# IO.net
KiCad netlist of a schematic drawn in Altium Designer
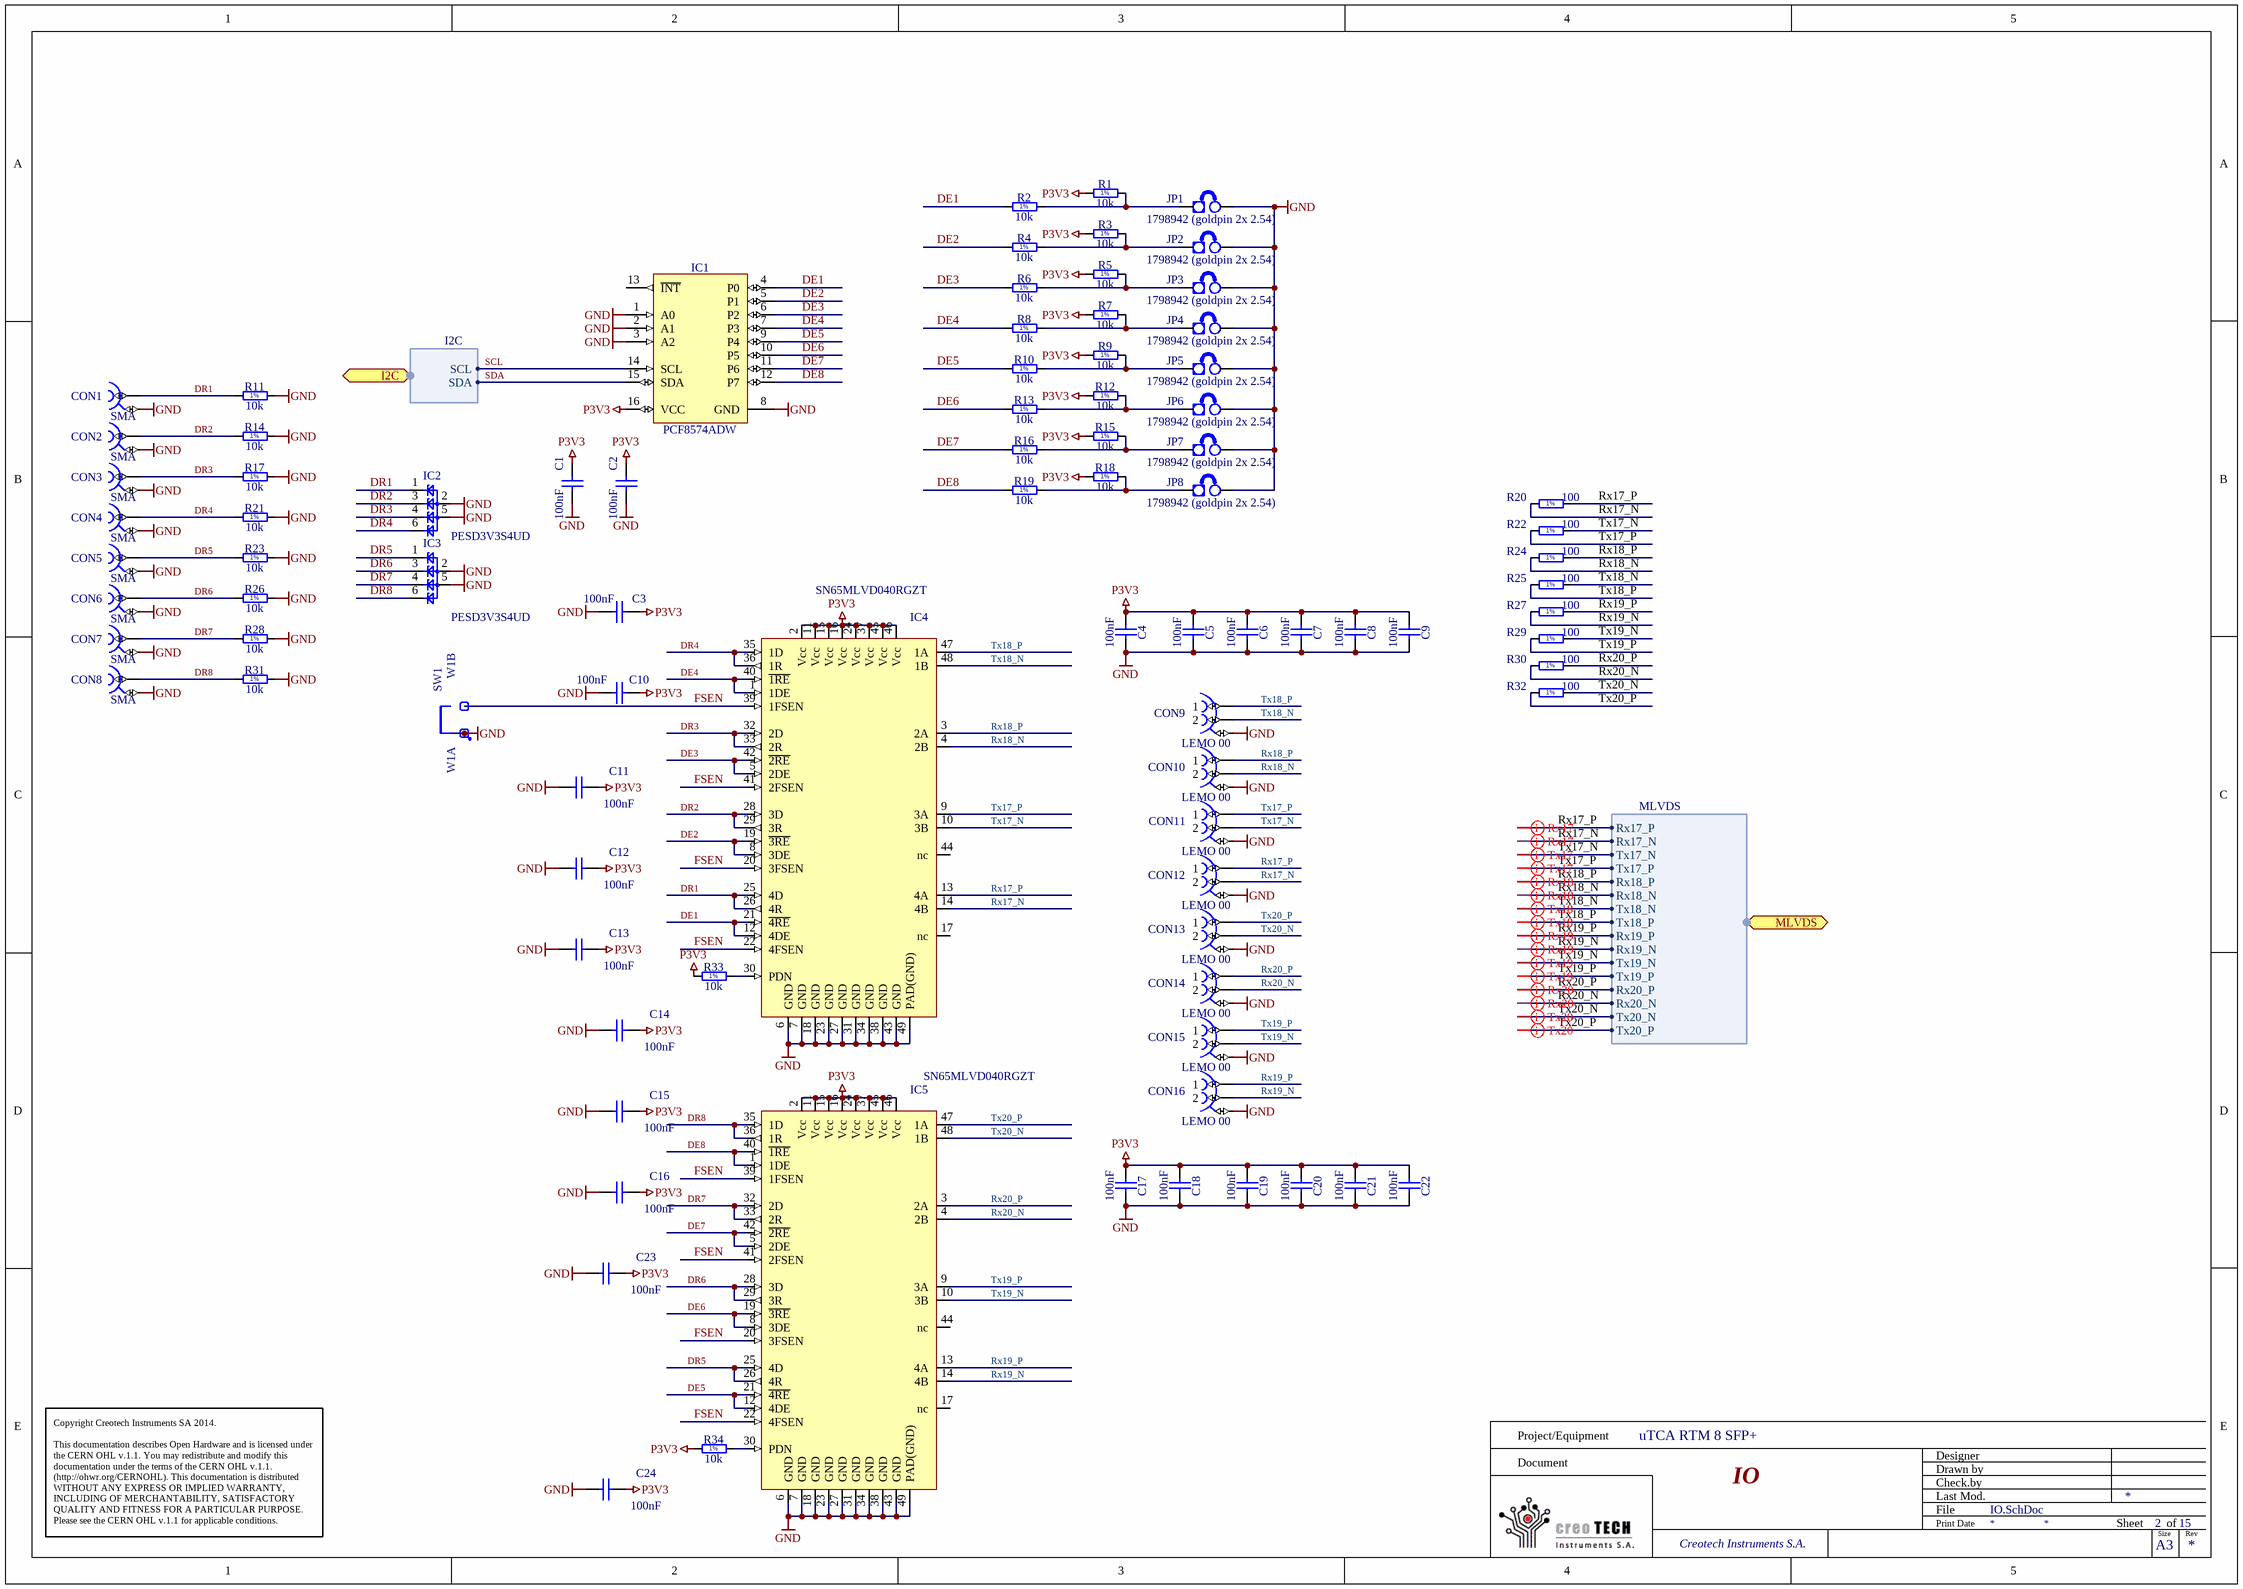
[diagram p0: IO.SchDoc]

(export (version "E")
  (design (tool "Eeschema 10.0.6"))
  (components
    (comp (ref "C1")
      (value "100nF")
      (footprint "CAPC0603X33N")
      (description "Non-polarised capacitor")
      (fields (field (name "PART NUMBER") "CC0201_100NF_6.3V_10%_X5R") (field (name "VOLTAGE") "6.3V"))
      (libsource (lib "Capacitors") (part "Capacitor - non polarized"))
    )
    (comp (ref "C2")
      (value "100nF")
      (footprint "CAPC0603X33N")
      (description "Non-polarised capacitor")
      (fields (field (name "PART NUMBER") "CC0201_100NF_6.3V_10%_X5R") (field (name "VOLTAGE") "6.3V"))
      (libsource (lib "Capacitors") (part "Capacitor - non polarized"))
    )
    (comp (ref "C3")
      (value "100nF")
      (footprint "CAPC0603X33N")
      (description "Non-polarised capacitor")
      (fields (field (name "PART NUMBER") "CC0201_100NF_6.3V_10%_X5R") (field (name "VOLTAGE") "6.3V"))
      (libsource (lib "Capacitors") (part "Capacitor - non polarized"))
    )
    (comp (ref "C4")
      (value "100nF")
      (footprint "CAPC0603X33N")
      (description "Non-polarised capacitor")
      (fields (field (name "PART NUMBER") "CC0201_100NF_6.3V_10%_X5R") (field (name "VOLTAGE") "6.3V"))
      (libsource (lib "Capacitors") (part "Capacitor - non polarized"))
    )
    (comp (ref "C5")
      (value "100nF")
      (footprint "CAPC0603X33N")
      (description "Non-polarised capacitor")
      (fields (field (name "PART NUMBER") "CC0201_100NF_6.3V_10%_X5R") (field (name "VOLTAGE") "6.3V"))
      (libsource (lib "Capacitors") (part "Capacitor - non polarized"))
    )
    (comp (ref "C6")
      (value "100nF")
      (footprint "CAPC0603X33N")
      (description "Non-polarised capacitor")
      (fields (field (name "PART NUMBER") "CC0201_100NF_6.3V_10%_X5R") (field (name "VOLTAGE") "6.3V"))
      (libsource (lib "Capacitors") (part "Capacitor - non polarized"))
    )
    (comp (ref "C7")
      (value "100nF")
      (footprint "CAPC0603X33N")
      (description "Non-polarised capacitor")
      (fields (field (name "PART NUMBER") "CC0201_100NF_6.3V_10%_X5R") (field (name "VOLTAGE") "6.3V"))
      (libsource (lib "Capacitors") (part "Capacitor - non polarized"))
    )
    (comp (ref "C8")
      (value "100nF")
      (footprint "CAPC0603X33N")
      (description "Non-polarised capacitor")
      (fields (field (name "PART NUMBER") "CC0201_100NF_6.3V_10%_X5R") (field (name "VOLTAGE") "6.3V"))
      (libsource (lib "Capacitors") (part "Capacitor - non polarized"))
    )
    (comp (ref "C9")
      (value "100nF")
      (footprint "CAPC0603X33N")
      (description "Non-polarised capacitor")
      (fields (field (name "PART NUMBER") "CC0201_100NF_6.3V_10%_X5R") (field (name "VOLTAGE") "6.3V"))
      (libsource (lib "Capacitors") (part "Capacitor - non polarized"))
    )
    (comp (ref "C10")
      (value "100nF")
      (footprint "CAPC0603X33N")
      (description "Non-polarised capacitor")
      (fields (field (name "PART NUMBER") "CC0201_100NF_6.3V_10%_X5R") (field (name "VOLTAGE") "6.3V"))
      (libsource (lib "Capacitors") (part "Capacitor - non polarized"))
    )
    (comp (ref "C11")
      (value "100nF")
      (footprint "CAPC0603X33N")
      (description "Non-polarised capacitor")
      (fields (field (name "PART NUMBER") "CC0201_100NF_6.3V_10%_X5R") (field (name "VOLTAGE") "6.3V"))
      (libsource (lib "Capacitors") (part "Capacitor - non polarized"))
    )
    (comp (ref "C12")
      (value "100nF")
      (footprint "CAPC0603X33N")
      (description "Non-polarised capacitor")
      (fields (field (name "PART NUMBER") "CC0201_100NF_6.3V_10%_X5R") (field (name "VOLTAGE") "6.3V"))
      (libsource (lib "Capacitors") (part "Capacitor - non polarized"))
    )
    (comp (ref "C13")
      (value "100nF")
      (footprint "CAPC0603X33N")
      (description "Non-polarised capacitor")
      (fields (field (name "PART NUMBER") "CC0201_100NF_6.3V_10%_X5R") (field (name "VOLTAGE") "6.3V"))
      (libsource (lib "Capacitors") (part "Capacitor - non polarized"))
    )
    (comp (ref "C14")
      (value "100nF")
      (footprint "CAPC0603X33N")
      (description "Non-polarised capacitor")
      (fields (field (name "PART NUMBER") "CC0201_100NF_6.3V_10%_X5R") (field (name "VOLTAGE") "6.3V"))
      (libsource (lib "Capacitors") (part "Capacitor - non polarized"))
    )
    (comp (ref "C15")
      (value "100nF")
      (footprint "CAPC0603X33N")
      (description "Non-polarised capacitor")
      (fields (field (name "PART NUMBER") "CC0201_100NF_6.3V_10%_X5R") (field (name "VOLTAGE") "6.3V"))
      (libsource (lib "Capacitors") (part "Capacitor - non polarized"))
    )
    (comp (ref "C16")
      (value "100nF")
      (footprint "CAPC0603X33N")
      (description "Non-polarised capacitor")
      (fields (field (name "PART NUMBER") "CC0201_100NF_6.3V_10%_X5R") (field (name "VOLTAGE") "6.3V"))
      (libsource (lib "Capacitors") (part "Capacitor - non polarized"))
    )
    (comp (ref "C17")
      (value "100nF")
      (footprint "CAPC0603X33N")
      (description "Non-polarised capacitor")
      (fields (field (name "PART NUMBER") "CC0201_100NF_6.3V_10%_X5R") (field (name "VOLTAGE") "6.3V"))
      (libsource (lib "Capacitors") (part "Capacitor - non polarized"))
    )
    (comp (ref "C18")
      (value "100nF")
      (footprint "CAPC0603X33N")
      (description "Non-polarised capacitor")
      (fields (field (name "PART NUMBER") "CC0201_100NF_6.3V_10%_X5R") (field (name "VOLTAGE") "6.3V"))
      (libsource (lib "Capacitors") (part "Capacitor - non polarized"))
    )
    (comp (ref "C19")
      (value "100nF")
      (footprint "CAPC0603X33N")
      (description "Non-polarised capacitor")
      (fields (field (name "PART NUMBER") "CC0201_100NF_6.3V_10%_X5R") (field (name "VOLTAGE") "6.3V"))
      (libsource (lib "Capacitors") (part "Capacitor - non polarized"))
    )
    (comp (ref "C20")
      (value "100nF")
      (footprint "CAPC0603X33N")
      (description "Non-polarised capacitor")
      (fields (field (name "PART NUMBER") "CC0201_100NF_6.3V_10%_X5R") (field (name "VOLTAGE") "6.3V"))
      (libsource (lib "Capacitors") (part "Capacitor - non polarized"))
    )
    (comp (ref "C21")
      (value "100nF")
      (footprint "CAPC0603X33N")
      (description "Non-polarised capacitor")
      (fields (field (name "PART NUMBER") "CC0201_100NF_6.3V_10%_X5R") (field (name "VOLTAGE") "6.3V"))
      (libsource (lib "Capacitors") (part "Capacitor - non polarized"))
    )
    (comp (ref "C22")
      (value "100nF")
      (footprint "CAPC0603X33N")
      (description "Non-polarised capacitor")
      (fields (field (name "PART NUMBER") "CC0201_100NF_6.3V_10%_X5R") (field (name "VOLTAGE") "6.3V"))
      (libsource (lib "Capacitors") (part "Capacitor - non polarized"))
    )
    (comp (ref "C23")
      (value "100nF")
      (footprint "CAPC0603X33N")
      (description "Non-polarised capacitor")
      (fields (field (name "PART NUMBER") "CC0201_100NF_6.3V_10%_X5R") (field (name "VOLTAGE") "6.3V"))
      (libsource (lib "Capacitors") (part "Capacitor - non polarized"))
    )
    (comp (ref "C24")
      (value "100nF")
      (footprint "CAPC0603X33N")
      (description "Non-polarised capacitor")
      (fields (field (name "PART NUMBER") "CC0201_100NF_6.3V_10%_X5R") (field (name "VOLTAGE") "6.3V"))
      (libsource (lib "Capacitors") (part "Capacitor - non polarized"))
    )
    (comp (ref "CON1")
      (value "SMA")
      (footprint "HUBER-SUHNER_85 SMA-50-0-101/111 NE")
      (fields
        (field (name "PART NUMBER") "HUBER-SUHNER_85_SMA-50-0-101/111_NE")
        (field (name "MANUFACTURER") "HUBER+SUHNER")
        (field (name "MANUFACTURER PART NUMBER") "85_SMA-50-0-101/111_NE")
      )
      (libsource (lib "Connectors") (part "Coax_1Female_1Shield"))
    )
    (comp (ref "CON2")
      (value "SMA")
      (footprint "HUBER-SUHNER_85 SMA-50-0-101/111 NE")
      (fields
        (field (name "PART NUMBER") "HUBER-SUHNER_85_SMA-50-0-101/111_NE")
        (field (name "MANUFACTURER") "HUBER+SUHNER")
        (field (name "MANUFACTURER PART NUMBER") "85_SMA-50-0-101/111_NE")
      )
      (libsource (lib "Connectors") (part "Coax_1Female_1Shield"))
    )
    (comp (ref "CON3")
      (value "SMA")
      (footprint "HUBER-SUHNER_85 SMA-50-0-101/111 NE")
      (fields
        (field (name "PART NUMBER") "HUBER-SUHNER_85_SMA-50-0-101/111_NE")
        (field (name "MANUFACTURER") "HUBER+SUHNER")
        (field (name "MANUFACTURER PART NUMBER") "85_SMA-50-0-101/111_NE")
      )
      (libsource (lib "Connectors") (part "Coax_1Female_1Shield"))
    )
    (comp (ref "CON4")
      (value "SMA")
      (footprint "HUBER-SUHNER_85 SMA-50-0-101/111 NE")
      (fields
        (field (name "PART NUMBER") "HUBER-SUHNER_85_SMA-50-0-101/111_NE")
        (field (name "MANUFACTURER") "HUBER+SUHNER")
        (field (name "MANUFACTURER PART NUMBER") "85_SMA-50-0-101/111_NE")
      )
      (libsource (lib "Connectors") (part "Coax_1Female_1Shield"))
    )
    (comp (ref "CON5")
      (value "SMA")
      (footprint "HUBER-SUHNER_85 SMA-50-0-101/111 NE")
      (fields
        (field (name "PART NUMBER") "HUBER-SUHNER_85_SMA-50-0-101/111_NE")
        (field (name "MANUFACTURER") "HUBER+SUHNER")
        (field (name "MANUFACTURER PART NUMBER") "85_SMA-50-0-101/111_NE")
      )
      (libsource (lib "Connectors") (part "Coax_1Female_1Shield"))
    )
    (comp (ref "CON6")
      (value "SMA")
      (footprint "HUBER-SUHNER_85 SMA-50-0-101/111 NE")
      (fields
        (field (name "PART NUMBER") "HUBER-SUHNER_85_SMA-50-0-101/111_NE")
        (field (name "MANUFACTURER") "HUBER+SUHNER")
        (field (name "MANUFACTURER PART NUMBER") "85_SMA-50-0-101/111_NE")
      )
      (libsource (lib "Connectors") (part "Coax_1Female_1Shield"))
    )
    (comp (ref "CON7")
      (value "SMA")
      (footprint "HUBER-SUHNER_85 SMA-50-0-101/111 NE")
      (fields
        (field (name "PART NUMBER") "HUBER-SUHNER_85_SMA-50-0-101/111_NE")
        (field (name "MANUFACTURER") "HUBER+SUHNER")
        (field (name "MANUFACTURER PART NUMBER") "85_SMA-50-0-101/111_NE")
      )
      (libsource (lib "Connectors") (part "Coax_1Female_1Shield"))
    )
    (comp (ref "CON8")
      (value "SMA")
      (footprint "HUBER-SUHNER_85 SMA-50-0-101/111 NE")
      (fields
        (field (name "PART NUMBER") "HUBER-SUHNER_85_SMA-50-0-101/111_NE")
        (field (name "MANUFACTURER") "HUBER+SUHNER")
        (field (name "MANUFACTURER PART NUMBER") "85_SMA-50-0-101/111_NE")
      )
      (libsource (lib "Connectors") (part "Coax_1Female_1Shield"))
    )
    (comp (ref "CON9")
      (value "LEMO 00")
      (footprint "LEMO_EPG.00.302.NLN")
      (fields
        (field (name "PART NUMBER") "LEMO_EPG.00.302.NLN")
        (field (name "MANUFACTURER") "LEMO")
        (field (name "MANUFACTURER PART NUMBER") "EPG.00.302.NLN")
      )
      (libsource (lib "Connectors") (part "Coax_2Female_1Shield"))
    )
    (comp (ref "CON10")
      (value "LEMO 00")
      (footprint "LEMO_EPG.00.302.NLN")
      (fields
        (field (name "PART NUMBER") "LEMO_EPG.00.302.NLN")
        (field (name "MANUFACTURER") "LEMO")
        (field (name "MANUFACTURER PART NUMBER") "EPG.00.302.NLN")
      )
      (libsource (lib "Connectors") (part "Coax_2Female_1Shield"))
    )
    (comp (ref "CON11")
      (value "LEMO 00")
      (footprint "LEMO_EPG.00.302.NLN")
      (fields
        (field (name "PART NUMBER") "LEMO_EPG.00.302.NLN")
        (field (name "MANUFACTURER") "LEMO")
        (field (name "MANUFACTURER PART NUMBER") "EPG.00.302.NLN")
      )
      (libsource (lib "Connectors") (part "Coax_2Female_1Shield"))
    )
    (comp (ref "CON12")
      (value "LEMO 00")
      (footprint "LEMO_EPG.00.302.NLN")
      (fields
        (field (name "PART NUMBER") "LEMO_EPG.00.302.NLN")
        (field (name "MANUFACTURER") "LEMO")
        (field (name "MANUFACTURER PART NUMBER") "EPG.00.302.NLN")
      )
      (libsource (lib "Connectors") (part "Coax_2Female_1Shield"))
    )
    (comp (ref "CON13")
      (value "LEMO 00")
      (footprint "LEMO_EPG.00.302.NLN")
      (fields
        (field (name "PART NUMBER") "LEMO_EPG.00.302.NLN")
        (field (name "MANUFACTURER") "LEMO")
        (field (name "MANUFACTURER PART NUMBER") "EPG.00.302.NLN")
      )
      (libsource (lib "Connectors") (part "Coax_2Female_1Shield"))
    )
    (comp (ref "CON14")
      (value "LEMO 00")
      (footprint "LEMO_EPG.00.302.NLN")
      (fields
        (field (name "PART NUMBER") "LEMO_EPG.00.302.NLN")
        (field (name "MANUFACTURER") "LEMO")
        (field (name "MANUFACTURER PART NUMBER") "EPG.00.302.NLN")
      )
      (libsource (lib "Connectors") (part "Coax_2Female_1Shield"))
    )
    (comp (ref "CON15")
      (value "LEMO 00")
      (footprint "LEMO_EPG.00.302.NLN")
      (fields
        (field (name "PART NUMBER") "LEMO_EPG.00.302.NLN")
        (field (name "MANUFACTURER") "LEMO")
        (field (name "MANUFACTURER PART NUMBER") "EPG.00.302.NLN")
      )
      (libsource (lib "Connectors") (part "Coax_2Female_1Shield"))
    )
    (comp (ref "CON16")
      (value "LEMO 00")
      (footprint "LEMO_EPG.00.302.NLN")
      (fields
        (field (name "PART NUMBER") "LEMO_EPG.00.302.NLN")
        (field (name "MANUFACTURER") "LEMO")
        (field (name "MANUFACTURER PART NUMBER") "EPG.00.302.NLN")
      )
      (libsource (lib "Connectors") (part "Coax_2Female_1Shield"))
    )
    (comp (ref "IC1")
      (value "PCF8574ADW")
      (footprint "SOIC127P1030X265-16N")
      (description "Remote 8-bit I/O Expander For I2C Bus")
      (fields (field (name "MANUFACTURER") "TEXAS INSTRUMENTS"))
      (libsource (lib "ICs And Semiconductors") (part "PCF8574ADW"))
    )
    (comp (ref "IC2")
      (value "PESD3V3S4UD")
      (footprint "SOT457")
      (description "3.3V TVS")
      (libsource (lib "LIBRARY_SCH") (part "D_TVS_PESD3V3S4UD"))
    )
    (comp (ref "IC3")
      (value "PESD3V3S4UD")
      (footprint "SOT457")
      (description "3.3V TVS")
      (libsource (lib "LIBRARY_SCH") (part "D_TVS_PESD3V3S4UD"))
    )
    (comp (ref "IC4")
      (value "SN65MLVD040RGZT")
      (footprint "QFN48L")
      (libsource (lib "LIBRARY_SCH") (part "IFC_SN65MLVD040"))
    )
    (comp (ref "IC5")
      (value "SN65MLVD040RGZT")
      (footprint "QFN48L")
      (libsource (lib "LIBRARY_SCH") (part "IFC_SN65MLVD040"))
    )
    (comp (ref "JP1")
      (value "1798942 (goldpin 2x 2.54)")
      (footprint "HEADER2x1 2.54mm")
      (description "Jumper")
      (libsource (lib "Misc") (part "JUMPER"))
    )
    (comp (ref "JP2")
      (value "1798942 (goldpin 2x 2.54)")
      (footprint "HEADER2x1 2.54mm")
      (description "Jumper")
      (libsource (lib "Misc") (part "JUMPER"))
    )
    (comp (ref "JP3")
      (value "1798942 (goldpin 2x 2.54)")
      (footprint "HEADER2x1 2.54mm")
      (description "Jumper")
      (libsource (lib "Misc") (part "JUMPER"))
    )
    (comp (ref "JP4")
      (value "1798942 (goldpin 2x 2.54)")
      (footprint "HEADER2x1 2.54mm")
      (description "Jumper")
      (libsource (lib "Misc") (part "JUMPER"))
    )
    (comp (ref "JP5")
      (value "1798942 (goldpin 2x 2.54)")
      (footprint "HEADER2x1 2.54mm")
      (description "Jumper")
      (libsource (lib "Misc") (part "JUMPER"))
    )
    (comp (ref "JP6")
      (value "1798942 (goldpin 2x 2.54)")
      (footprint "HEADER2x1 2.54mm")
      (description "Jumper")
      (libsource (lib "Misc") (part "JUMPER"))
    )
    (comp (ref "JP7")
      (value "1798942 (goldpin 2x 2.54)")
      (footprint "HEADER2x1 2.54mm")
      (description "Jumper")
      (libsource (lib "Misc") (part "JUMPER"))
    )
    (comp (ref "JP8")
      (value "1798942 (goldpin 2x 2.54)")
      (footprint "HEADER2x1 2.54mm")
      (description "Jumper")
      (libsource (lib "Misc") (part "JUMPER"))
    )
    (comp (ref "R1")
      (value "10k")
      (footprint "RESC1005X40N")
      (description "Resistor - 1%")
      (fields (field (name "PART NUMBER") "R0402_10K_1%_0.0625W_100PPM") (field (name "POWER") "0.0625W"))
      (libsource (lib "Resistors") (part "Resistor - 1%"))
    )
    (comp (ref "R2")
      (value "10k")
      (footprint "RESC1005X40N")
      (description "Resistor - 1%")
      (fields (field (name "PART NUMBER") "R0402_10K_1%_0.0625W_100PPM") (field (name "POWER") "0.0625W"))
      (libsource (lib "Resistors") (part "Resistor - 1%"))
    )
    (comp (ref "R3")
      (value "10k")
      (footprint "RESC1005X40N")
      (description "Resistor - 1%")
      (fields (field (name "PART NUMBER") "R0402_10K_1%_0.0625W_100PPM") (field (name "POWER") "0.0625W"))
      (libsource (lib "Resistors") (part "Resistor - 1%"))
    )
    (comp (ref "R4")
      (value "10k")
      (footprint "RESC1005X40N")
      (description "Resistor - 1%")
      (fields (field (name "PART NUMBER") "R0402_10K_1%_0.0625W_100PPM") (field (name "POWER") "0.0625W"))
      (libsource (lib "Resistors") (part "Resistor - 1%"))
    )
    (comp (ref "R5")
      (value "10k")
      (footprint "RESC1005X40N")
      (description "Resistor - 1%")
      (fields (field (name "PART NUMBER") "R0402_10K_1%_0.0625W_100PPM") (field (name "POWER") "0.0625W"))
      (libsource (lib "Resistors") (part "Resistor - 1%"))
    )
    (comp (ref "R6")
      (value "10k")
      (footprint "RESC1005X40N")
      (description "Resistor - 1%")
      (fields (field (name "PART NUMBER") "R0402_10K_1%_0.0625W_100PPM") (field (name "POWER") "0.0625W"))
      (libsource (lib "Resistors") (part "Resistor - 1%"))
    )
    (comp (ref "R7")
      (value "10k")
      (footprint "RESC1005X40N")
      (description "Resistor - 1%")
      (fields (field (name "PART NUMBER") "R0402_10K_1%_0.0625W_100PPM") (field (name "POWER") "0.0625W"))
      (libsource (lib "Resistors") (part "Resistor - 1%"))
    )
    (comp (ref "R8")
      (value "10k")
      (footprint "RESC1005X40N")
      (description "Resistor - 1%")
      (fields (field (name "PART NUMBER") "R0402_10K_1%_0.0625W_100PPM") (field (name "POWER") "0.0625W"))
      (libsource (lib "Resistors") (part "Resistor - 1%"))
    )
    (comp (ref "R9")
      (value "10k")
      (footprint "RESC1005X40N")
      (description "Resistor - 1%")
      (fields (field (name "PART NUMBER") "R0402_10K_1%_0.0625W_100PPM") (field (name "POWER") "0.0625W"))
      (libsource (lib "Resistors") (part "Resistor - 1%"))
    )
    (comp (ref "R10")
      (value "10k")
      (footprint "RESC1005X40N")
      (description "Resistor - 1%")
      (fields (field (name "PART NUMBER") "R0402_10K_1%_0.0625W_100PPM") (field (name "POWER") "0.0625W"))
      (libsource (lib "Resistors") (part "Resistor - 1%"))
    )
    (comp (ref "R11")
      (value "10k")
      (footprint "RESC1005X40N")
      (description "Resistor - 1%")
      (fields (field (name "PART NUMBER") "R0402_10K_1%_0.0625W_100PPM") (field (name "POWER") "0.0625W"))
      (libsource (lib "Resistors") (part "Resistor - 1%"))
    )
    (comp (ref "R12")
      (value "10k")
      (footprint "RESC1005X40N")
      (description "Resistor - 1%")
      (fields (field (name "PART NUMBER") "R0402_10K_1%_0.0625W_100PPM") (field (name "POWER") "0.0625W"))
      (libsource (lib "Resistors") (part "Resistor - 1%"))
    )
    (comp (ref "R13")
      (value "10k")
      (footprint "RESC1005X40N")
      (description "Resistor - 1%")
      (fields (field (name "PART NUMBER") "R0402_10K_1%_0.0625W_100PPM") (field (name "POWER") "0.0625W"))
      (libsource (lib "Resistors") (part "Resistor - 1%"))
    )
    (comp (ref "R14")
      (value "10k")
      (footprint "RESC1005X40N")
      (description "Resistor - 1%")
      (fields (field (name "PART NUMBER") "R0402_10K_1%_0.0625W_100PPM") (field (name "POWER") "0.0625W"))
      (libsource (lib "Resistors") (part "Resistor - 1%"))
    )
    (comp (ref "R15")
      (value "10k")
      (footprint "RESC1005X40N")
      (description "Resistor - 1%")
      (fields (field (name "PART NUMBER") "R0402_10K_1%_0.0625W_100PPM") (field (name "POWER") "0.0625W"))
      (libsource (lib "Resistors") (part "Resistor - 1%"))
    )
    (comp (ref "R16")
      (value "10k")
      (footprint "RESC1005X40N")
      (description "Resistor - 1%")
      (fields (field (name "PART NUMBER") "R0402_10K_1%_0.0625W_100PPM") (field (name "POWER") "0.0625W"))
      (libsource (lib "Resistors") (part "Resistor - 1%"))
    )
    (comp (ref "R17")
      (value "10k")
      (footprint "RESC1005X40N")
      (description "Resistor - 1%")
      (fields (field (name "PART NUMBER") "R0402_10K_1%_0.0625W_100PPM") (field (name "POWER") "0.0625W"))
      (libsource (lib "Resistors") (part "Resistor - 1%"))
    )
    (comp (ref "R18")
      (value "10k")
      (footprint "RESC1005X40N")
      (description "Resistor - 1%")
      (fields (field (name "PART NUMBER") "R0402_10K_1%_0.0625W_100PPM") (field (name "POWER") "0.0625W"))
      (libsource (lib "Resistors") (part "Resistor - 1%"))
    )
    (comp (ref "R19")
      (value "10k")
      (footprint "RESC1005X40N")
      (description "Resistor - 1%")
      (fields (field (name "PART NUMBER") "R0402_10K_1%_0.0625W_100PPM") (field (name "POWER") "0.0625W"))
      (libsource (lib "Resistors") (part "Resistor - 1%"))
    )
    (comp (ref "R20")
      (value "100")
      (footprint "RESC1005X40N")
      (description "Resistor - 1%")
      (fields (field (name "PART NUMBER") "R0402_100R_1%_0.0625W_100PPM") (field (name "POWER") "0.0625W"))
      (libsource (lib "Resistors") (part "Resistor - 1%"))
    )
    (comp (ref "R21")
      (value "10k")
      (footprint "RESC1005X40N")
      (description "Resistor - 1%")
      (fields (field (name "PART NUMBER") "R0402_10K_1%_0.0625W_100PPM") (field (name "POWER") "0.0625W"))
      (libsource (lib "Resistors") (part "Resistor - 1%"))
    )
    (comp (ref "R22")
      (value "100")
      (footprint "RESC1005X40N")
      (description "Resistor - 1%")
      (fields (field (name "PART NUMBER") "R0402_100R_1%_0.0625W_100PPM") (field (name "POWER") "0.0625W"))
      (libsource (lib "Resistors") (part "Resistor - 1%"))
    )
    (comp (ref "R23")
      (value "10k")
      (footprint "RESC1005X40N")
      (description "Resistor - 1%")
      (fields (field (name "PART NUMBER") "R0402_10K_1%_0.0625W_100PPM") (field (name "POWER") "0.0625W"))
      (libsource (lib "Resistors") (part "Resistor - 1%"))
    )
    (comp (ref "R24")
      (value "100")
      (footprint "RESC1005X40N")
      (description "Resistor - 1%")
      (fields (field (name "PART NUMBER") "R0402_100R_1%_0.0625W_100PPM") (field (name "POWER") "0.0625W"))
      (libsource (lib "Resistors") (part "Resistor - 1%"))
    )
    (comp (ref "R25")
      (value "100")
      (footprint "RESC1005X40N")
      (description "Resistor - 1%")
      (fields (field (name "PART NUMBER") "R0402_100R_1%_0.0625W_100PPM") (field (name "POWER") "0.0625W"))
      (libsource (lib "Resistors") (part "Resistor - 1%"))
    )
    (comp (ref "R26")
      (value "10k")
      (footprint "RESC1005X40N")
      (description "Resistor - 1%")
      (fields (field (name "PART NUMBER") "R0402_10K_1%_0.0625W_100PPM") (field (name "POWER") "0.0625W"))
      (libsource (lib "Resistors") (part "Resistor - 1%"))
    )
    (comp (ref "R27")
      (value "100")
      (footprint "RESC1005X40N")
      (description "Resistor - 1%")
      (fields (field (name "PART NUMBER") "R0402_100R_1%_0.0625W_100PPM") (field (name "POWER") "0.0625W"))
      (libsource (lib "Resistors") (part "Resistor - 1%"))
    )
    (comp (ref "R28")
      (value "10k")
      (footprint "RESC1005X40N")
      (description "Resistor - 1%")
      (fields (field (name "PART NUMBER") "R0402_10K_1%_0.0625W_100PPM") (field (name "POWER") "0.0625W"))
      (libsource (lib "Resistors") (part "Resistor - 1%"))
    )
    (comp (ref "R29")
      (value "100")
      (footprint "RESC1005X40N")
      (description "Resistor - 1%")
      (fields (field (name "PART NUMBER") "R0402_100R_1%_0.0625W_100PPM") (field (name "POWER") "0.0625W"))
      (libsource (lib "Resistors") (part "Resistor - 1%"))
    )
    (comp (ref "R30")
      (value "100")
      (footprint "RESC1005X40N")
      (description "Resistor - 1%")
      (fields (field (name "PART NUMBER") "R0402_100R_1%_0.0625W_100PPM") (field (name "POWER") "0.0625W"))
      (libsource (lib "Resistors") (part "Resistor - 1%"))
    )
    (comp (ref "R31")
      (value "10k")
      (footprint "RESC1005X40N")
      (description "Resistor - 1%")
      (fields (field (name "PART NUMBER") "R0402_10K_1%_0.0625W_100PPM") (field (name "POWER") "0.0625W"))
      (libsource (lib "Resistors") (part "Resistor - 1%"))
    )
    (comp (ref "R32")
      (value "100")
      (footprint "RESC1005X40N")
      (description "Resistor - 1%")
      (fields (field (name "PART NUMBER") "R0402_100R_1%_0.0625W_100PPM") (field (name "POWER") "0.0625W"))
      (libsource (lib "Resistors") (part "Resistor - 1%"))
    )
    (comp (ref "R33")
      (value "10k")
      (footprint "RESC1005X40N")
      (description "Resistor - 1%")
      (fields (field (name "PART NUMBER") "R0402_10K_1%_0.0625W_100PPM") (field (name "POWER") "0.0625W"))
      (libsource (lib "Resistors") (part "Resistor - 1%"))
    )
    (comp (ref "R34")
      (value "10k")
      (footprint "RESC1005X40N")
      (description "Resistor - 1%")
      (fields (field (name "PART NUMBER") "R0402_10K_1%_0.0625W_100PPM") (field (name "POWER") "0.0625W"))
      (libsource (lib "Resistors") (part "Resistor - 1%"))
    )
    (comp (ref "SW1")
      (value "Jumper Type1")
      (footprint "JUMPER_BLACK_INSULATED_2.54MM")
      (description "Jumper 1 Pin")
      (fields
        (field (name "PART NUMBER") "COMATEL_313.1730.0.00.40.0")
        (field (name "MANUFACTURER") "KONTEK COMATEL")
      )
      (libsource (lib "Connectors") (part "Jumper Type1"))
    )
    (comp (ref "W1")
      (value "Test Point")
      (footprint "COMATEL_385.0358.1.02.400")
      (description "2 Mini Wire-Wrap Contact Strip Header")
      (fields
        (field (name "PART NUMBER") "COMATEL_385.0358.1.02.400")
        (field (name "MANUFACTURER") "KONTEK COMATEL")
      )
      (libsource (lib "Connectors") (part "Wire-Wrap Contact x2"))
    )
  )
  (nets
    (net (code "3") (name "/DE1") (class "Default")
      (node (ref "IC1") (pin "4") (pinfunction "P0_4") (pintype "bidirectional"))
      (node (ref "IC4") (pin "12") (pinfunction "4DE_12") (pintype "input"))
      (node (ref "IC4") (pin "21") (pinfunction "~{4RE}_21") (pintype "input"))
      (node (ref "R2") (pin "1") (pinfunction "1_1") (pintype "passive"))
    )
    (net (code "4") (name "/DE2") (class "Default")
      (node (ref "IC1") (pin "5") (pinfunction "P1_5") (pintype "bidirectional"))
      (node (ref "IC4") (pin "19") (pinfunction "~{3RE}_19") (pintype "input"))
      (node (ref "IC4") (pin "8") (pinfunction "3DE_8") (pintype "input"))
      (node (ref "R4") (pin "1") (pinfunction "1_1") (pintype "passive"))
    )
    (net (code "5") (name "/DE3") (class "Default")
      (node (ref "IC1") (pin "6") (pinfunction "P2_6") (pintype "bidirectional"))
      (node (ref "IC4") (pin "42") (pinfunction "~{2RE}_42") (pintype "input"))
      (node (ref "IC4") (pin "5") (pinfunction "2DE_5") (pintype "input"))
      (node (ref "R6") (pin "1") (pinfunction "1_1") (pintype "passive"))
    )
    (net (code "6") (name "/DE4") (class "Default")
      (node (ref "IC1") (pin "7") (pinfunction "P3_7") (pintype "bidirectional"))
      (node (ref "IC4") (pin "1") (pinfunction "1DE_1") (pintype "input"))
      (node (ref "IC4") (pin "40") (pinfunction "~{1RE}_40") (pintype "input"))
      (node (ref "R8") (pin "1") (pinfunction "1_1") (pintype "passive"))
    )
    (net (code "7") (name "/DE5") (class "Default")
      (node (ref "IC1") (pin "9") (pinfunction "P4_9") (pintype "bidirectional"))
      (node (ref "IC5") (pin "12") (pinfunction "4DE_12") (pintype "input"))
      (node (ref "IC5") (pin "21") (pinfunction "~{4RE}_21") (pintype "input"))
      (node (ref "R10") (pin "1") (pinfunction "1_1") (pintype "passive"))
    )
    (net (code "8") (name "/DE6") (class "Default")
      (node (ref "IC1") (pin "10") (pinfunction "P5_10") (pintype "bidirectional"))
      (node (ref "IC5") (pin "19") (pinfunction "~{3RE}_19") (pintype "input"))
      (node (ref "IC5") (pin "8") (pinfunction "3DE_8") (pintype "input"))
      (node (ref "R13") (pin "1") (pinfunction "1_1") (pintype "passive"))
    )
    (net (code "9") (name "/DE7") (class "Default")
      (node (ref "IC1") (pin "11") (pinfunction "P6_11") (pintype "bidirectional"))
      (node (ref "IC5") (pin "42") (pinfunction "~{2RE}_42") (pintype "input"))
      (node (ref "IC5") (pin "5") (pinfunction "2DE_5") (pintype "input"))
      (node (ref "R16") (pin "1") (pinfunction "1_1") (pintype "passive"))
    )
    (net (code "10") (name "/DE8") (class "Default")
      (node (ref "IC1") (pin "12") (pinfunction "P7_12") (pintype "bidirectional"))
      (node (ref "IC5") (pin "1") (pinfunction "1DE_1") (pintype "input"))
      (node (ref "IC5") (pin "40") (pinfunction "~{1RE}_40") (pintype "input"))
      (node (ref "R19") (pin "1") (pinfunction "1_1") (pintype "passive"))
    )
    (net (code "11") (name "/DR1") (class "Default")
      (node (ref "CON1") (pin "1") (pinfunction "1_1") (pintype "bidirectional"))
      (node (ref "IC2") (pin "1") (pinfunction "1_1") (pintype "passive"))
      (node (ref "IC4") (pin "25") (pinfunction "4D_25") (pintype "input"))
      (node (ref "IC4") (pin "26") (pinfunction "4R_26") (pintype "output"))
      (node (ref "R11") (pin "1") (pinfunction "1_1") (pintype "passive"))
    )
    (net (code "12") (name "/DR2") (class "Default")
      (node (ref "CON2") (pin "1") (pinfunction "1_1") (pintype "bidirectional"))
      (node (ref "IC2") (pin "3") (pinfunction "3_3") (pintype "passive"))
      (node (ref "IC4") (pin "28") (pinfunction "3D_28") (pintype "input"))
      (node (ref "IC4") (pin "29") (pinfunction "3R_29") (pintype "output"))
      (node (ref "R14") (pin "1") (pinfunction "1_1") (pintype "passive"))
    )
    (net (code "13") (name "/DR3") (class "Default")
      (node (ref "CON3") (pin "1") (pinfunction "1_1") (pintype "bidirectional"))
      (node (ref "IC2") (pin "4") (pinfunction "4_4") (pintype "passive"))
      (node (ref "IC4") (pin "32") (pinfunction "2D_32") (pintype "input"))
      (node (ref "IC4") (pin "33") (pinfunction "2R_33") (pintype "output"))
      (node (ref "R17") (pin "1") (pinfunction "1_1") (pintype "passive"))
    )
    (net (code "14") (name "/DR4") (class "Default")
      (node (ref "CON4") (pin "1") (pinfunction "1_1") (pintype "bidirectional"))
      (node (ref "IC2") (pin "6") (pinfunction "6_6") (pintype "passive"))
      (node (ref "IC4") (pin "35") (pinfunction "1D_35") (pintype "input"))
      (node (ref "IC4") (pin "36") (pinfunction "1R_36") (pintype "output"))
      (node (ref "R21") (pin "1") (pinfunction "1_1") (pintype "passive"))
    )
    (net (code "15") (name "/DR5") (class "Default")
      (node (ref "CON5") (pin "1") (pinfunction "1_1") (pintype "bidirectional"))
      (node (ref "IC3") (pin "1") (pinfunction "1_1") (pintype "passive"))
      (node (ref "IC5") (pin "25") (pinfunction "4D_25") (pintype "input"))
      (node (ref "IC5") (pin "26") (pinfunction "4R_26") (pintype "output"))
      (node (ref "R23") (pin "1") (pinfunction "1_1") (pintype "passive"))
    )
    (net (code "16") (name "/DR6") (class "Default")
      (node (ref "CON6") (pin "1") (pinfunction "1_1") (pintype "bidirectional"))
      (node (ref "IC3") (pin "3") (pinfunction "3_3") (pintype "passive"))
      (node (ref "IC5") (pin "28") (pinfunction "3D_28") (pintype "input"))
      (node (ref "IC5") (pin "29") (pinfunction "3R_29") (pintype "output"))
      (node (ref "R26") (pin "1") (pinfunction "1_1") (pintype "passive"))
    )
    (net (code "17") (name "/DR7") (class "Default")
      (node (ref "CON7") (pin "1") (pinfunction "1_1") (pintype "bidirectional"))
      (node (ref "IC3") (pin "4") (pinfunction "4_4") (pintype "passive"))
      (node (ref "IC5") (pin "32") (pinfunction "2D_32") (pintype "input"))
      (node (ref "IC5") (pin "33") (pinfunction "2R_33") (pintype "output"))
      (node (ref "R28") (pin "1") (pinfunction "1_1") (pintype "passive"))
    )
    (net (code "18") (name "/DR8") (class "Default")
      (node (ref "CON8") (pin "1") (pinfunction "1_1") (pintype "bidirectional"))
      (node (ref "IC3") (pin "6") (pinfunction "6_6") (pintype "passive"))
      (node (ref "IC5") (pin "35") (pinfunction "1D_35") (pintype "input"))
      (node (ref "IC5") (pin "36") (pinfunction "1R_36") (pintype "output"))
      (node (ref "R31") (pin "1") (pinfunction "1_1") (pintype "passive"))
    )
    (net (code "19") (name "/FSEN") (class "Default")
      (node (ref "IC4") (pin "20") (pinfunction "3FSEN_20") (pintype "input"))
      (node (ref "IC4") (pin "22") (pinfunction "4FSEN_22") (pintype "input"))
      (node (ref "IC4") (pin "39") (pinfunction "1FSEN_39") (pintype "input"))
      (node (ref "IC4") (pin "41") (pinfunction "2FSEN_41") (pintype "input"))
      (node (ref "IC5") (pin "20") (pinfunction "3FSEN_20") (pintype "input"))
      (node (ref "IC5") (pin "22") (pinfunction "4FSEN_22") (pintype "input"))
      (node (ref "IC5") (pin "39") (pinfunction "1FSEN_39") (pintype "input"))
      (node (ref "IC5") (pin "41") (pinfunction "2FSEN_41") (pintype "input"))
      (node (ref "W1") (pin "2") (pinfunction "2_2") (pintype "bidirectional"))
    )
    (net (code "20") (name "/Rx17_N") (class "Default")
      (node (ref "CON12") (pin "2") (pinfunction "2_2") (pintype "bidirectional"))
      (node (ref "IC4") (pin "14") (pinfunction "4B_14") (pintype "bidirectional"))
      (node (ref "R20") (pin "1") (pinfunction "1_1") (pintype "passive"))
    )
    (net (code "21") (name "/Rx17_P") (class "Default")
      (node (ref "CON12") (pin "1") (pinfunction "1_1") (pintype "bidirectional"))
      (node (ref "IC4") (pin "13") (pinfunction "4A_13") (pintype "bidirectional"))
      (node (ref "R20") (pin "2") (pinfunction "2_2") (pintype "passive"))
    )
    (net (code "22") (name "/Rx18_N") (class "Default")
      (node (ref "CON10") (pin "2") (pinfunction "2_2") (pintype "bidirectional"))
      (node (ref "IC4") (pin "4") (pinfunction "2B_4") (pintype "bidirectional"))
      (node (ref "R24") (pin "1") (pinfunction "1_1") (pintype "passive"))
    )
    (net (code "23") (name "/Rx18_P") (class "Default")
      (node (ref "CON10") (pin "1") (pinfunction "1_1") (pintype "bidirectional"))
      (node (ref "IC4") (pin "3") (pinfunction "2A_3") (pintype "bidirectional"))
      (node (ref "R24") (pin "2") (pinfunction "2_2") (pintype "passive"))
    )
    (net (code "24") (name "/Rx19_N") (class "Default")
      (node (ref "CON16") (pin "2") (pinfunction "2_2") (pintype "bidirectional"))
      (node (ref "IC5") (pin "14") (pinfunction "4B_14") (pintype "bidirectional"))
      (node (ref "R27") (pin "1") (pinfunction "1_1") (pintype "passive"))
    )
    (net (code "25") (name "/Rx19_P") (class "Default")
      (node (ref "CON16") (pin "1") (pinfunction "1_1") (pintype "bidirectional"))
      (node (ref "IC5") (pin "13") (pinfunction "4A_13") (pintype "bidirectional"))
      (node (ref "R27") (pin "2") (pinfunction "2_2") (pintype "passive"))
    )
    (net (code "26") (name "/Rx20_N") (class "Default")
      (node (ref "CON14") (pin "2") (pinfunction "2_2") (pintype "bidirectional"))
      (node (ref "IC5") (pin "4") (pinfunction "2B_4") (pintype "bidirectional"))
      (node (ref "R30") (pin "1") (pinfunction "1_1") (pintype "passive"))
    )
    (net (code "27") (name "/Rx20_P") (class "Default")
      (node (ref "CON14") (pin "1") (pinfunction "1_1") (pintype "bidirectional"))
      (node (ref "IC5") (pin "3") (pinfunction "2A_3") (pintype "bidirectional"))
      (node (ref "R30") (pin "2") (pinfunction "2_2") (pintype "passive"))
    )
    (net (code "28") (name "/SCL") (class "Default")
      (node (ref "IC1") (pin "14") (pinfunction "SCL_14") (pintype "input"))
    )
    (net (code "29") (name "/SDA") (class "Default")
      (node (ref "IC1") (pin "15") (pinfunction "SDA_15") (pintype "bidirectional"))
    )
    (net (code "30") (name "/Tx17_N") (class "Default")
      (node (ref "CON11") (pin "2") (pinfunction "2_2") (pintype "bidirectional"))
      (node (ref "IC4") (pin "10") (pinfunction "3B_10") (pintype "bidirectional"))
      (node (ref "R22") (pin "2") (pinfunction "2_2") (pintype "passive"))
    )
    (net (code "31") (name "/Tx17_P") (class "Default")
      (node (ref "CON11") (pin "1") (pinfunction "1_1") (pintype "bidirectional"))
      (node (ref "IC4") (pin "9") (pinfunction "3A_9") (pintype "bidirectional"))
      (node (ref "R22") (pin "1") (pinfunction "1_1") (pintype "passive"))
    )
    (net (code "32") (name "/Tx18_N") (class "Default")
      (node (ref "CON9") (pin "2") (pinfunction "2_2") (pintype "bidirectional"))
      (node (ref "IC4") (pin "48") (pinfunction "1B_48") (pintype "bidirectional"))
      (node (ref "R25") (pin "2") (pinfunction "2_2") (pintype "passive"))
    )
    (net (code "33") (name "/Tx18_P") (class "Default")
      (node (ref "CON9") (pin "1") (pinfunction "1_1") (pintype "bidirectional"))
      (node (ref "IC4") (pin "47") (pinfunction "1A_47") (pintype "bidirectional"))
      (node (ref "R25") (pin "1") (pinfunction "1_1") (pintype "passive"))
    )
    (net (code "34") (name "/Tx19_N") (class "Default")
      (node (ref "CON15") (pin "2") (pinfunction "2_2") (pintype "bidirectional"))
      (node (ref "IC5") (pin "10") (pinfunction "3B_10") (pintype "bidirectional"))
      (node (ref "R29") (pin "2") (pinfunction "2_2") (pintype "passive"))
    )
    (net (code "35") (name "/Tx19_P") (class "Default")
      (node (ref "CON15") (pin "1") (pinfunction "1_1") (pintype "bidirectional"))
      (node (ref "IC5") (pin "9") (pinfunction "3A_9") (pintype "bidirectional"))
      (node (ref "R29") (pin "1") (pinfunction "1_1") (pintype "passive"))
    )
    (net (code "36") (name "/Tx20_N") (class "Default")
      (node (ref "CON13") (pin "2") (pinfunction "2_2") (pintype "bidirectional"))
      (node (ref "IC5") (pin "48") (pinfunction "1B_48") (pintype "bidirectional"))
      (node (ref "R32") (pin "2") (pinfunction "2_2") (pintype "passive"))
    )
    (net (code "37") (name "/Tx20_P") (class "Default")
      (node (ref "CON13") (pin "1") (pinfunction "1_1") (pintype "bidirectional"))
      (node (ref "IC5") (pin "47") (pinfunction "1A_47") (pintype "bidirectional"))
      (node (ref "R32") (pin "1") (pinfunction "1_1") (pintype "passive"))
    )
    (net (code "40") (name "GND") (class "Default")
      (node (ref "C1") (pin "1") (pinfunction "1_1") (pintype "passive"))
      (node (ref "C10") (pin "1") (pinfunction "1_1") (pintype "passive"))
      (node (ref "C11") (pin "2") (pinfunction "2_2") (pintype "passive"))
      (node (ref "C12") (pin "2") (pinfunction "2_2") (pintype "passive"))
      (node (ref "C13") (pin "2") (pinfunction "2_2") (pintype "passive"))
      (node (ref "C14") (pin "2") (pinfunction "2_2") (pintype "passive"))
      (node (ref "C15") (pin "2") (pinfunction "2_2") (pintype "passive"))
      (node (ref "C16") (pin "2") (pinfunction "2_2") (pintype "passive"))
      (node (ref "C17") (pin "2") (pinfunction "2_2") (pintype "passive"))
      (node (ref "C18") (pin "2") (pinfunction "2_2") (pintype "passive"))
      (node (ref "C19") (pin "2") (pinfunction "2_2") (pintype "passive"))
      (node (ref "C2") (pin "1") (pinfunction "1_1") (pintype "passive"))
      (node (ref "C20") (pin "2") (pinfunction "2_2") (pintype "passive"))
      (node (ref "C21") (pin "2") (pinfunction "2_2") (pintype "passive"))
      (node (ref "C22") (pin "2") (pinfunction "2_2") (pintype "passive"))
      (node (ref "C23") (pin "2") (pinfunction "2_2") (pintype "passive"))
      (node (ref "C24") (pin "2") (pinfunction "2_2") (pintype "passive"))
      (node (ref "C3") (pin "1") (pinfunction "1_1") (pintype "passive"))
      (node (ref "C4") (pin "2") (pinfunction "2_2") (pintype "passive"))
      (node (ref "C5") (pin "2") (pinfunction "2_2") (pintype "passive"))
      (node (ref "C6") (pin "2") (pinfunction "2_2") (pintype "passive"))
      (node (ref "C7") (pin "2") (pinfunction "2_2") (pintype "passive"))
      (node (ref "C8") (pin "2") (pinfunction "2_2") (pintype "passive"))
      (node (ref "C9") (pin "2") (pinfunction "2_2") (pintype "passive"))
      (node (ref "CON1") (pin "2") (pinfunction "2_2") (pintype "bidirectional"))
      (node (ref "CON10") (pin "3") (pinfunction "3_3") (pintype "bidirectional"))
      (node (ref "CON11") (pin "3") (pinfunction "3_3") (pintype "bidirectional"))
      (node (ref "CON12") (pin "3") (pinfunction "3_3") (pintype "bidirectional"))
      (node (ref "CON13") (pin "3") (pinfunction "3_3") (pintype "bidirectional"))
      (node (ref "CON14") (pin "3") (pinfunction "3_3") (pintype "bidirectional"))
      (node (ref "CON15") (pin "3") (pinfunction "3_3") (pintype "bidirectional"))
      (node (ref "CON16") (pin "3") (pinfunction "3_3") (pintype "bidirectional"))
      (node (ref "CON2") (pin "2") (pinfunction "2_2") (pintype "bidirectional"))
      (node (ref "CON3") (pin "2") (pinfunction "2_2") (pintype "bidirectional"))
      (node (ref "CON4") (pin "2") (pinfunction "2_2") (pintype "bidirectional"))
      (node (ref "CON5") (pin "2") (pinfunction "2_2") (pintype "bidirectional"))
      (node (ref "CON6") (pin "2") (pinfunction "2_2") (pintype "bidirectional"))
      (node (ref "CON7") (pin "2") (pinfunction "2_2") (pintype "bidirectional"))
      (node (ref "CON8") (pin "2") (pinfunction "2_2") (pintype "bidirectional"))
      (node (ref "CON9") (pin "3") (pinfunction "3_3") (pintype "bidirectional"))
      (node (ref "IC1") (pin "1") (pinfunction "A0_1") (pintype "input"))
      (node (ref "IC1") (pin "2") (pinfunction "A1_2") (pintype "input"))
      (node (ref "IC1") (pin "3") (pinfunction "A2_3") (pintype "input"))
      (node (ref "IC1") (pin "8") (pinfunction "GND_8") (pintype "power_in"))
      (node (ref "IC2") (pin "2") (pinfunction "2_2") (pintype "passive"))
      (node (ref "IC2") (pin "5") (pinfunction "5_5") (pintype "passive"))
      (node (ref "IC3") (pin "2") (pinfunction "2_2") (pintype "passive"))
      (node (ref "IC3") (pin "5") (pinfunction "5_5") (pintype "passive"))
      (node (ref "IC4") (pin "18") (pinfunction "GND_18") (pintype "power_in"))
      (node (ref "IC4") (pin "23") (pinfunction "GND_23") (pintype "power_in"))
      (node (ref "IC4") (pin "27") (pinfunction "GND_27") (pintype "power_in"))
      (node (ref "IC4") (pin "31") (pinfunction "GND_31") (pintype "power_in"))
      (node (ref "IC4") (pin "34") (pinfunction "GND_34") (pintype "power_in"))
      (node (ref "IC4") (pin "38") (pinfunction "GND_38") (pintype "power_in"))
      (node (ref "IC4") (pin "43") (pinfunction "GND_43") (pintype "power_in"))
      (node (ref "IC4") (pin "49") (pinfunction "PAD(GND)_49") (pintype "power_in"))
      (node (ref "IC4") (pin "6") (pinfunction "GND_6") (pintype "power_in"))
      (node (ref "IC4") (pin "7") (pinfunction "GND_7") (pintype "power_in"))
      (node (ref "IC5") (pin "18") (pinfunction "GND_18") (pintype "power_in"))
      (node (ref "IC5") (pin "23") (pinfunction "GND_23") (pintype "power_in"))
      (node (ref "IC5") (pin "27") (pinfunction "GND_27") (pintype "power_in"))
      (node (ref "IC5") (pin "31") (pinfunction "GND_31") (pintype "power_in"))
      (node (ref "IC5") (pin "34") (pinfunction "GND_34") (pintype "power_in"))
      (node (ref "IC5") (pin "38") (pinfunction "GND_38") (pintype "power_in"))
      (node (ref "IC5") (pin "43") (pinfunction "GND_43") (pintype "power_in"))
      (node (ref "IC5") (pin "49") (pinfunction "PAD(GND)_49") (pintype "power_in"))
      (node (ref "IC5") (pin "6") (pinfunction "GND_6") (pintype "power_in"))
      (node (ref "IC5") (pin "7") (pinfunction "GND_7") (pintype "power_in"))
      (node (ref "JP1") (pin "2") (pinfunction "E2_2") (pintype "passive"))
      (node (ref "JP2") (pin "2") (pinfunction "E2_2") (pintype "passive"))
      (node (ref "JP3") (pin "2") (pinfunction "E2_2") (pintype "passive"))
      (node (ref "JP4") (pin "2") (pinfunction "E2_2") (pintype "passive"))
      (node (ref "JP5") (pin "2") (pinfunction "E2_2") (pintype "passive"))
      (node (ref "JP6") (pin "2") (pinfunction "E2_2") (pintype "passive"))
      (node (ref "JP7") (pin "2") (pinfunction "E2_2") (pintype "passive"))
      (node (ref "JP8") (pin "2") (pinfunction "E2_2") (pintype "passive"))
      (node (ref "R11") (pin "2") (pinfunction "2_2") (pintype "passive"))
      (node (ref "R14") (pin "2") (pinfunction "2_2") (pintype "passive"))
      (node (ref "R17") (pin "2") (pinfunction "2_2") (pintype "passive"))
      (node (ref "R21") (pin "2") (pinfunction "2_2") (pintype "passive"))
      (node (ref "R23") (pin "2") (pinfunction "2_2") (pintype "passive"))
      (node (ref "R26") (pin "2") (pinfunction "2_2") (pintype "passive"))
      (node (ref "R28") (pin "2") (pinfunction "2_2") (pintype "passive"))
      (node (ref "R31") (pin "2") (pinfunction "2_2") (pintype "passive"))
      (node (ref "SW1") (pin "1") (pinfunction "1_1") (pintype "bidirectional"))
      (node (ref "W1") (pin "1") (pinfunction "1_1") (pintype "bidirectional"))
    )
    (net (code "41") (name "Net-(IC4-PDN)") (class "Default")
      (node (ref "IC4") (pin "30") (pinfunction "PDN_30") (pintype "input"))
      (node (ref "R33") (pin "2") (pinfunction "2_2") (pintype "passive"))
    )
    (net (code "42") (name "Net-(IC5-PDN)") (class "Default")
      (node (ref "IC5") (pin "30") (pinfunction "PDN_30") (pintype "input"))
      (node (ref "R34") (pin "2") (pinfunction "2_2") (pintype "passive"))
    )
    (net (code "43") (name "Net-(JP1-E1)") (class "Default")
      (node (ref "JP1") (pin "1") (pinfunction "E1_1") (pintype "passive"))
      (node (ref "R1") (pin "2") (pinfunction "2_2") (pintype "passive"))
      (node (ref "R2") (pin "2") (pinfunction "2_2") (pintype "passive"))
    )
    (net (code "44") (name "Net-(JP2-E1)") (class "Default")
      (node (ref "JP2") (pin "1") (pinfunction "E1_1") (pintype "passive"))
      (node (ref "R3") (pin "2") (pinfunction "2_2") (pintype "passive"))
      (node (ref "R4") (pin "2") (pinfunction "2_2") (pintype "passive"))
    )
    (net (code "45") (name "Net-(JP3-E1)") (class "Default")
      (node (ref "JP3") (pin "1") (pinfunction "E1_1") (pintype "passive"))
      (node (ref "R5") (pin "2") (pinfunction "2_2") (pintype "passive"))
      (node (ref "R6") (pin "2") (pinfunction "2_2") (pintype "passive"))
    )
    (net (code "46") (name "Net-(JP4-E1)") (class "Default")
      (node (ref "JP4") (pin "1") (pinfunction "E1_1") (pintype "passive"))
      (node (ref "R7") (pin "2") (pinfunction "2_2") (pintype "passive"))
      (node (ref "R8") (pin "2") (pinfunction "2_2") (pintype "passive"))
    )
    (net (code "47") (name "Net-(JP5-E1)") (class "Default")
      (node (ref "JP5") (pin "1") (pinfunction "E1_1") (pintype "passive"))
      (node (ref "R10") (pin "2") (pinfunction "2_2") (pintype "passive"))
      (node (ref "R9") (pin "2") (pinfunction "2_2") (pintype "passive"))
    )
    (net (code "48") (name "Net-(JP6-E1)") (class "Default")
      (node (ref "JP6") (pin "1") (pinfunction "E1_1") (pintype "passive"))
      (node (ref "R12") (pin "2") (pinfunction "2_2") (pintype "passive"))
      (node (ref "R13") (pin "2") (pinfunction "2_2") (pintype "passive"))
    )
    (net (code "49") (name "Net-(JP7-E1)") (class "Default")
      (node (ref "JP7") (pin "1") (pinfunction "E1_1") (pintype "passive"))
      (node (ref "R15") (pin "2") (pinfunction "2_2") (pintype "passive"))
      (node (ref "R16") (pin "2") (pinfunction "2_2") (pintype "passive"))
    )
    (net (code "50") (name "Net-(JP8-E1)") (class "Default")
      (node (ref "JP8") (pin "1") (pinfunction "E1_1") (pintype "passive"))
      (node (ref "R18") (pin "2") (pinfunction "2_2") (pintype "passive"))
      (node (ref "R19") (pin "2") (pinfunction "2_2") (pintype "passive"))
    )
    (net (code "51") (name "P3V3") (class "Default")
      (node (ref "C1") (pin "2") (pinfunction "2_2") (pintype "passive"))
      (node (ref "C10") (pin "2") (pinfunction "2_2") (pintype "passive"))
      (node (ref "C11") (pin "1") (pinfunction "1_1") (pintype "passive"))
      (node (ref "C12") (pin "1") (pinfunction "1_1") (pintype "passive"))
      (node (ref "C13") (pin "1") (pinfunction "1_1") (pintype "passive"))
      (node (ref "C14") (pin "1") (pinfunction "1_1") (pintype "passive"))
      (node (ref "C15") (pin "1") (pinfunction "1_1") (pintype "passive"))
      (node (ref "C16") (pin "1") (pinfunction "1_1") (pintype "passive"))
      (node (ref "C17") (pin "1") (pinfunction "1_1") (pintype "passive"))
      (node (ref "C18") (pin "1") (pinfunction "1_1") (pintype "passive"))
      (node (ref "C19") (pin "1") (pinfunction "1_1") (pintype "passive"))
      (node (ref "C2") (pin "2") (pinfunction "2_2") (pintype "passive"))
      (node (ref "C20") (pin "1") (pinfunction "1_1") (pintype "passive"))
      (node (ref "C21") (pin "1") (pinfunction "1_1") (pintype "passive"))
      (node (ref "C22") (pin "1") (pinfunction "1_1") (pintype "passive"))
      (node (ref "C23") (pin "1") (pinfunction "1_1") (pintype "passive"))
      (node (ref "C24") (pin "1") (pinfunction "1_1") (pintype "passive"))
      (node (ref "C3") (pin "2") (pinfunction "2_2") (pintype "passive"))
      (node (ref "C4") (pin "1") (pinfunction "1_1") (pintype "passive"))
      (node (ref "C5") (pin "1") (pinfunction "1_1") (pintype "passive"))
      (node (ref "C6") (pin "1") (pinfunction "1_1") (pintype "passive"))
      (node (ref "C7") (pin "1") (pinfunction "1_1") (pintype "passive"))
      (node (ref "C8") (pin "1") (pinfunction "1_1") (pintype "passive"))
      (node (ref "C9") (pin "1") (pinfunction "1_1") (pintype "passive"))
      (node (ref "IC1") (pin "16") (pinfunction "VCC_16") (pintype "bidirectional"))
      (node (ref "IC4") (pin "11") (pinfunction "Vcc_11") (pintype "power_in"))
      (node (ref "IC4") (pin "15") (pinfunction "Vcc_15") (pintype "power_in"))
      (node (ref "IC4") (pin "16") (pinfunction "Vcc_16") (pintype "power_in"))
      (node (ref "IC4") (pin "2") (pinfunction "Vcc_2") (pintype "power_in"))
      (node (ref "IC4") (pin "24") (pinfunction "Vcc_24") (pintype "power_in"))
      (node (ref "IC4") (pin "37") (pinfunction "Vcc_37") (pintype "power_in"))
      (node (ref "IC4") (pin "45") (pinfunction "Vcc_45") (pintype "power_in"))
      (node (ref "IC4") (pin "46") (pinfunction "Vcc_46") (pintype "power_in"))
      (node (ref "IC5") (pin "11") (pinfunction "Vcc_11") (pintype "power_in"))
      (node (ref "IC5") (pin "15") (pinfunction "Vcc_15") (pintype "power_in"))
      (node (ref "IC5") (pin "16") (pinfunction "Vcc_16") (pintype "power_in"))
      (node (ref "IC5") (pin "2") (pinfunction "Vcc_2") (pintype "power_in"))
      (node (ref "IC5") (pin "24") (pinfunction "Vcc_24") (pintype "power_in"))
      (node (ref "IC5") (pin "37") (pinfunction "Vcc_37") (pintype "power_in"))
      (node (ref "IC5") (pin "45") (pinfunction "Vcc_45") (pintype "power_in"))
      (node (ref "IC5") (pin "46") (pinfunction "Vcc_46") (pintype "power_in"))
      (node (ref "R1") (pin "1") (pinfunction "1_1") (pintype "passive"))
      (node (ref "R12") (pin "1") (pinfunction "1_1") (pintype "passive"))
      (node (ref "R15") (pin "1") (pinfunction "1_1") (pintype "passive"))
      (node (ref "R18") (pin "1") (pinfunction "1_1") (pintype "passive"))
      (node (ref "R3") (pin "1") (pinfunction "1_1") (pintype "passive"))
      (node (ref "R33") (pin "1") (pinfunction "1_1") (pintype "passive"))
      (node (ref "R34") (pin "1") (pinfunction "1_1") (pintype "passive"))
      (node (ref "R5") (pin "1") (pinfunction "1_1") (pintype "passive"))
      (node (ref "R7") (pin "1") (pinfunction "1_1") (pintype "passive"))
      (node (ref "R9") (pin "1") (pinfunction "1_1") (pintype "passive"))
    )
    (net (code "52") (name "unconnected-(IC1-~{INT}-Pad13)") (class "Default")
      (node (ref "IC1") (pin "13") (pinfunction "~{INT}_13") (pintype "output"))
    )
    (net (code "53") (name "unconnected-(IC4-nc-Pad17)") (class "Default")
      (node (ref "IC4") (pin "17") (pinfunction "nc_17") (pintype "passive"))
    )
    (net (code "54") (name "unconnected-(IC4-nc-Pad44)") (class "Default")
      (node (ref "IC4") (pin "44") (pinfunction "nc_44") (pintype "power_in"))
    )
    (net (code "55") (name "unconnected-(IC5-nc-Pad17)") (class "Default")
      (node (ref "IC5") (pin "17") (pinfunction "nc_17") (pintype "passive"))
    )
    (net (code "56") (name "unconnected-(IC5-nc-Pad44)") (class "Default")
      (node (ref "IC5") (pin "44") (pinfunction "nc_44") (pintype "power_in"))
    )
  )
)
